# esp8266-addon-card-v1a-open.net
KiCad netlist of a schematic drawn in EAGLE
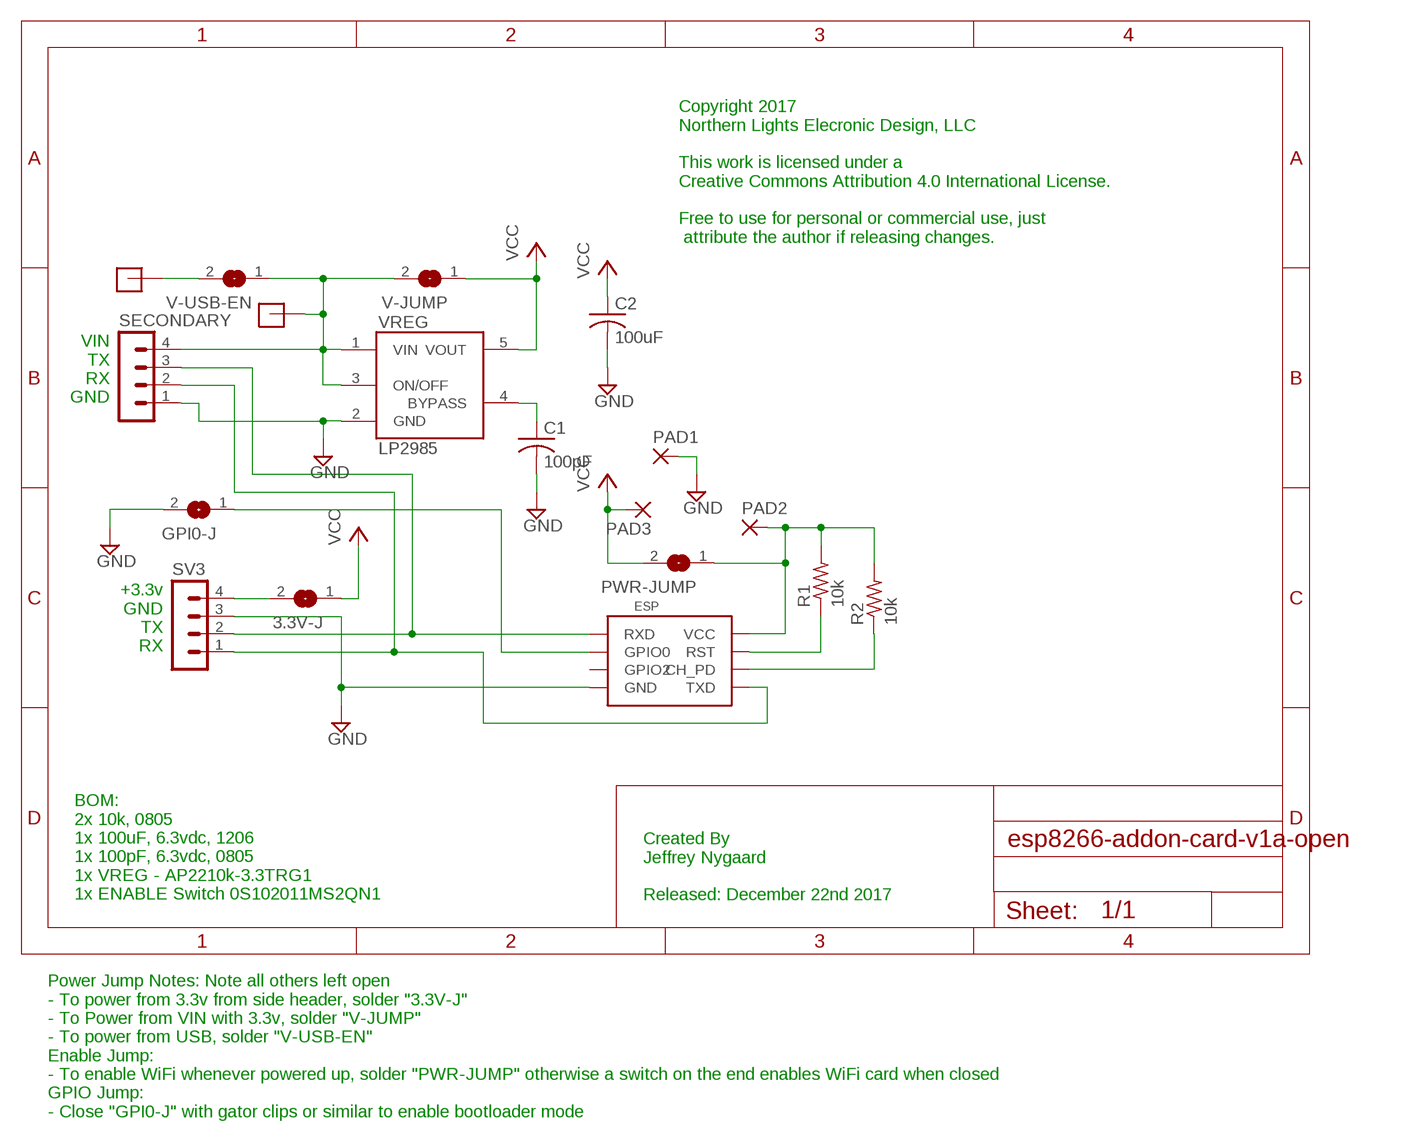
[diagram p0: schematic, sheet 1]

(export (version "E")
  (design (tool "Eeschema 10.0.6"))
  (components
    (comp (ref "3.3V-J")
      (value "SJ")
      (footprint "eagle-import:SJ")
      (libsource (lib "eagle-import") (part "SJ"))
    )
    (comp (ref "C1")
      (value "100pF")
      (footprint "eagle-import:C0805")
      (libsource (lib "eagle-import") (part "C-USC0805"))
    )
    (comp (ref "C2")
      (value "100uF")
      (footprint "eagle-import:C1206")
      (libsource (lib "eagle-import") (part "C-USC1206"))
    )
    (comp (ref "ESP")
      (value "ESP8266")
      (footprint "eagle-import:ESP8266-2")
      (libsource (lib "eagle-import") (part "ESP8266"))
    )
    (comp (ref "GPI0-J")
      (value "SJW")
      (footprint "eagle-import:SJW")
      (libsource (lib "eagle-import") (part "SJW"))
    )
    (comp (ref "PAD1")
      (value "SMD2")
      (footprint "eagle-import:SMD1,27-2,54")
      (libsource (lib "eagle-import") (part "SMD2"))
    )
    (comp (ref "PAD2")
      (value "SMD2")
      (footprint "eagle-import:SMD1,27-2,54")
      (libsource (lib "eagle-import") (part "SMD2"))
    )
    (comp (ref "PAD3")
      (value "SMD2")
      (footprint "eagle-import:SMD1,27-2,54")
      (libsource (lib "eagle-import") (part "SMD2"))
    )
    (comp (ref "PWR-JUMP")
      (value "SJ")
      (footprint "eagle-import:SJ")
      (libsource (lib "eagle-import") (part "SJ"))
    )
    (comp (ref "R1")
      (value "10k")
      (footprint "eagle-import:M0805")
      (libsource (lib "eagle-import") (part "R-US_M0805"))
    )
    (comp (ref "R2")
      (value "10k")
      (footprint "eagle-import:M0805")
      (libsource (lib "eagle-import") (part "R-US_M0805"))
    )
    (comp (ref "SECONDARY")
      (value "MA04-1")
      (footprint "eagle-import:MA04-1")
      (libsource (lib "eagle-import") (part "MA04-1"))
    )
    (comp (ref "SV3")
      (value "MA04-1")
      (footprint "eagle-import:MA04-1")
      (libsource (lib "eagle-import") (part "MA04-1"))
    )
    (comp (ref "V-JUMP")
      (value "SJ")
      (footprint "eagle-import:SJ")
      (libsource (lib "eagle-import") (part "SJ"))
    )
    (comp (ref "V-USB")
      (value "JUMPER")
      (footprint "eagle-import:JUMPER")
      (libsource (lib "eagle-import") (part "JUMPER"))
    )
    (comp (ref "V-USB-EN")
      (value "SJ")
      (footprint "eagle-import:SJ")
      (libsource (lib "eagle-import") (part "SJ"))
    )
    (comp (ref "VIN")
      (value "JUMPER")
      (footprint "eagle-import:JUMPER")
      (libsource (lib "eagle-import") (part "JUMPER"))
    )
    (comp (ref "VREG")
      (value "LP2985AIM5-3.3")
      (footprint "eagle-import:SOT25")
      (libsource (lib "eagle-import") (part "LP2985AIM5-3.3"))
    )
  )
  (nets
    (net (code "1") (name "GND") (class "Default")
      (node (ref "C1") (pin "2") (pinfunction "2_2") (pintype "passive"))
      (node (ref "C2") (pin "2") (pinfunction "2_2") (pintype "passive"))
      (node (ref "ESP") (pin "GND") (pinfunction "GND_GND") (pintype "bidirectional"))
      (node (ref "GPI0-J") (pin "2") (pinfunction "2_2") (pintype "passive"))
      (node (ref "PAD1") (pin "1") (pinfunction "P_1") (pintype "passive"))
      (node (ref "SECONDARY") (pin "1") (pinfunction "1_1") (pintype "passive"))
      (node (ref "SV3") (pin "3") (pinfunction "3_3") (pintype "passive"))
      (node (ref "VREG") (pin "2") (pinfunction "GND_2") (pintype "power_in"))
    )
    (net (code "2") (name "Net-(3.3V-J-Pad2)") (class "Default")
      (node (ref "3.3V-J") (pin "2") (pinfunction "2_2") (pintype "passive"))
      (node (ref "SV3") (pin "4") (pinfunction "4_4") (pintype "passive"))
    )
    (net (code "3") (name "Net-(ESP-PadCH_PD)") (class "Default")
      (node (ref "ESP") (pin "CH_PD") (pinfunction "CH_PD_CH_PD") (pintype "bidirectional"))
      (node (ref "R2") (pin "1") (pinfunction "1_1") (pintype "passive"))
    )
    (net (code "4") (name "Net-(ESP-PadGPIO0)") (class "Default")
      (node (ref "ESP") (pin "GPIO0") (pinfunction "GPIO0_GPIO0") (pintype "bidirectional"))
      (node (ref "GPI0-J") (pin "1") (pinfunction "1_1") (pintype "passive"))
    )
    (net (code "5") (name "Net-(ESP-PadRST)") (class "Default")
      (node (ref "ESP") (pin "RST") (pinfunction "RST_RST") (pintype "bidirectional"))
      (node (ref "R1") (pin "1") (pinfunction "1_1") (pintype "passive"))
    )
    (net (code "6") (name "Net-(ESP-PadRXD)") (class "Default")
      (node (ref "ESP") (pin "RXD") (pinfunction "RXD_RXD") (pintype "bidirectional"))
      (node (ref "SECONDARY") (pin "3") (pinfunction "3_3") (pintype "passive"))
      (node (ref "SV3") (pin "2") (pinfunction "2_2") (pintype "passive"))
    )
    (net (code "7") (name "Net-(ESP-PadTXD)") (class "Default")
      (node (ref "ESP") (pin "TXD") (pinfunction "TXD_TXD") (pintype "bidirectional"))
      (node (ref "SECONDARY") (pin "2") (pinfunction "2_2") (pintype "passive"))
      (node (ref "SV3") (pin "1") (pinfunction "1_1") (pintype "passive"))
    )
    (net (code "8") (name "Net-(PAD2-P)") (class "Default")
      (node (ref "ESP") (pin "VCC") (pinfunction "VCC_VCC") (pintype "bidirectional"))
      (node (ref "PAD2") (pin "1") (pinfunction "P_1") (pintype "passive"))
      (node (ref "PWR-JUMP") (pin "1") (pinfunction "1_1") (pintype "passive"))
      (node (ref "R1") (pin "2") (pinfunction "2_2") (pintype "passive"))
      (node (ref "R2") (pin "2") (pinfunction "2_2") (pintype "passive"))
    )
    (net (code "9") (name "Net-(V-USB-J1)") (class "Default")
      (node (ref "V-USB") (pin "2") (pinfunction "J1_2") (pintype "bidirectional"))
      (node (ref "V-USB-EN") (pin "2") (pinfunction "2_2") (pintype "passive"))
    )
    (net (code "10") (name "Net-(VIN-J1)") (class "Default")
      (node (ref "SECONDARY") (pin "4") (pinfunction "4_4") (pintype "passive"))
      (node (ref "V-JUMP") (pin "2") (pinfunction "2_2") (pintype "passive"))
      (node (ref "V-USB-EN") (pin "1") (pinfunction "1_1") (pintype "passive"))
      (node (ref "VIN") (pin "2") (pinfunction "J1_2") (pintype "bidirectional"))
      (node (ref "VREG") (pin "1") (pinfunction "VIN_1") (pintype "power_in"))
      (node (ref "VREG") (pin "3") (pinfunction "ON/OFF_3") (pintype "input"))
    )
    (net (code "11") (name "Net-(VREG-BYPASS)") (class "Default")
      (node (ref "C1") (pin "1") (pinfunction "1_1") (pintype "passive"))
      (node (ref "VREG") (pin "4") (pinfunction "BYPASS_4") (pintype "power_in"))
    )
    (net (code "12") (name "VCC") (class "Default")
      (node (ref "3.3V-J") (pin "1") (pinfunction "1_1") (pintype "passive"))
      (node (ref "C2") (pin "1") (pinfunction "1_1") (pintype "passive"))
      (node (ref "PAD3") (pin "1") (pinfunction "P_1") (pintype "passive"))
      (node (ref "PWR-JUMP") (pin "2") (pinfunction "2_2") (pintype "passive"))
      (node (ref "V-JUMP") (pin "1") (pinfunction "1_1") (pintype "passive"))
      (node (ref "VREG") (pin "5") (pinfunction "VOUT_5") (pintype "power_in"))
    )
    (net (code "13") (name "unconnected-(ESP-PadGPIO2)") (class "Default")
      (node (ref "ESP") (pin "GPIO2") (pinfunction "GPIO2_GPIO2") (pintype "bidirectional"))
    )
  )
)
